# UM202.net
KiCad netlist of a schematic drawn in Altium Designer
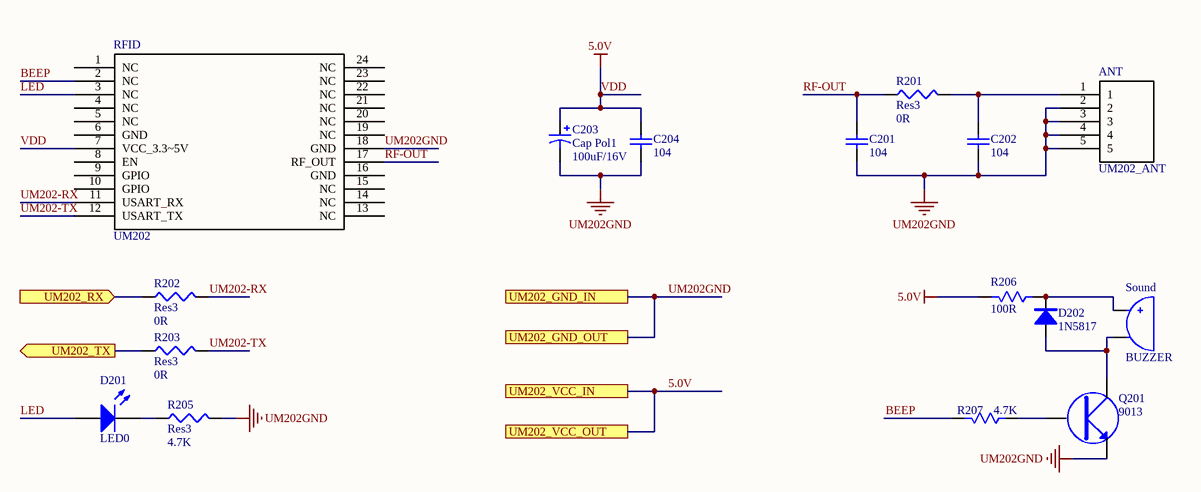
[diagram p0: UM202.SchDoc]

(export (version "E")
  (design (tool "Eeschema 10.0.6"))
  (components
    (comp (ref "ANT") (value "UM202_ANT") (libsource (lib "Schlib1") (part "UM202_ANT")))
    (comp (ref "C201")
      (value "104")
      (footprint "RAD-0.3")
      (description "Capacitor")
      (fields (field (name "PUBLISHER") "Altium Limited"))
      (libsource (lib "Miscellaneous Devices") (part "Cap"))
    )
    (comp (ref "C202")
      (value "104")
      (footprint "RAD-0.3")
      (description "Capacitor")
      (fields (field (name "PUBLISHER") "Altium Limited"))
      (libsource (lib "Miscellaneous Devices") (part "Cap"))
    )
    (comp (ref "C203")
      (value "Cap Pol1")
      (footprint "RB7.6-15")
      (description "Polarized Capacitor (Radial)")
      (fields (field (name "ALTIUM_VALUE") "100uF/16V") (field (name "PUBLISHER") "Altium Limited"))
      (libsource (lib "Miscellaneous Devices") (part "Cap Pol1"))
    )
    (comp (ref "C204")
      (value "104")
      (footprint "RAD-0.3")
      (description "Capacitor")
      (fields (field (name "PUBLISHER") "Altium Limited"))
      (libsource (lib "Miscellaneous Devices") (part "Cap"))
    )
    (comp (ref "D201")
      (value "LED0")
      (footprint "LED-0")
      (description "Typical INFRARED GaAs LED")
      (fields (field (name "PUBLISHER") "Altium Limited"))
      (libsource (lib "Miscellaneous Devices") (part "LED0"))
    )
    (comp (ref "D202")
      (value "1N5817")
      (footprint "YUWEI_LIB:SOD-323")
      (description "Diode")
      (libsource (lib "*") (part "DIODE"))
    )
    (comp (ref "Q201") (value "9013") (libsource (lib "Schlib1") (part "9013")))
    (comp (ref "R201")
      (value "Res3")
      (footprint "J1-0603")
      (description "Resistor")
      (fields (field (name "ALTIUM_VALUE") "0R") (field (name "PUBLISHER") "Altium Limited"))
      (libsource (lib "Miscellaneous Devices") (part "Res3"))
    )
    (comp (ref "R202")
      (value "Res3")
      (footprint "J1-0603")
      (description "Resistor")
      (fields (field (name "ALTIUM_VALUE") "0R") (field (name "PUBLISHER") "Altium Limited"))
      (libsource (lib "Miscellaneous Devices") (part "Res3"))
    )
    (comp (ref "R203")
      (value "Res3")
      (footprint "J1-0603")
      (description "Resistor")
      (fields (field (name "ALTIUM_VALUE") "0R") (field (name "PUBLISHER") "Altium Limited"))
      (libsource (lib "Miscellaneous Devices") (part "Res3"))
    )
    (comp (ref "R205")
      (value "Res3")
      (footprint "J1-0603")
      (description "Resistor")
      (fields (field (name "ALTIUM_VALUE") "4.7K") (field (name "PUBLISHER") "Altium Limited"))
      (libsource (lib "Miscellaneous Devices") (part "Res3"))
    )
    (comp (ref "R206") (value "100R") (footprint "YUWEI_LIB:0603R-M") (libsource (lib "*") (part "RES1")))
    (comp (ref "R207") (value "4.7K") (footprint "YUWEI_LIB:0603R-M") (libsource (lib "*") (part "RES1")))
    (comp (ref "RFID") (value "UM202") (libsource (lib "Schlib1") (part "UM202")))
    (comp (ref "Sound")
      (value "BUZZER")
      (footprint "YUWEI_LIB:BUZZER-SMD")
      (description "Buzzer")
      (libsource (lib "*") (part "BUZZER"))
    )
  )
  (nets
    (net (code "1") (name "/BEEP") (class "Default")
      (node (ref "R207") (pin "1") (pinfunction "1_1") (pintype "passive"))
      (node (ref "RFID") (pin "2") (pinfunction "NC_2") (pintype "passive"))
    )
    (net (code "2") (name "/LED") (class "Default")
      (node (ref "D201") (pin "1") (pinfunction "A_1") (pintype "passive"))
      (node (ref "RFID") (pin "3") (pinfunction "NC_3") (pintype "passive"))
    )
    (net (code "3") (name "/RF-OUT") (class "Default")
      (node (ref "C201") (pin "2") (pinfunction "2_2") (pintype "passive"))
      (node (ref "R201") (pin "1") (pinfunction "1_1") (pintype "passive"))
      (node (ref "RFID") (pin "17") (pinfunction "RF_OUT_17") (pintype "passive"))
    )
    (net (code "4") (name "/UM202-RX") (class "Default")
      (node (ref "R202") (pin "2") (pinfunction "2_2") (pintype "passive"))
      (node (ref "RFID") (pin "11") (pinfunction "USART_RX_11") (pintype "passive"))
    )
    (net (code "5") (name "/UM202-TX") (class "Default")
      (node (ref "R203") (pin "2") (pinfunction "2_2") (pintype "passive"))
      (node (ref "RFID") (pin "12") (pinfunction "USART_TX_12") (pintype "passive"))
    )
    (net (code "6") (name "/UM202_RX") (class "Default")
      (node (ref "R202") (pin "1") (pinfunction "1_1") (pintype "passive"))
    )
    (net (code "7") (name "/UM202_TX") (class "Default")
      (node (ref "R203") (pin "1") (pinfunction "1_1") (pintype "passive"))
    )
    (net (code "8") (name "5.0V") (class "Default")
      (node (ref "C203") (pin "1") (pinfunction "1_1") (pintype "passive"))
      (node (ref "C204") (pin "2") (pinfunction "2_2") (pintype "passive"))
      (node (ref "R206") (pin "1") (pinfunction "1_1") (pintype "passive"))
      (node (ref "RFID") (pin "7") (pinfunction "VCC_3.3~5V_7") (pintype "passive"))
    )
    (net (code "9") (name "Net-(ANT-Pad1)") (class "Default")
      (node (ref "ANT") (pin "1") (pinfunction "1_1") (pintype "passive"))
      (node (ref "C202") (pin "2") (pinfunction "2_2") (pintype "passive"))
      (node (ref "R201") (pin "2") (pinfunction "2_2") (pintype "passive"))
    )
    (net (code "10") (name "Net-(D201-K)") (class "Default")
      (node (ref "D201") (pin "2") (pinfunction "K_2") (pintype "passive"))
      (node (ref "R205") (pin "1") (pinfunction "1_1") (pintype "passive"))
    )
    (net (code "11") (name "Net-(Q201-Pad1)") (class "Default")
      (node (ref "Q201") (pin "1") (pinfunction "1_1") (pintype "passive"))
      (node (ref "R207") (pin "2") (pinfunction "2_2") (pintype "passive"))
    )
    (net (code "12") (name "Net-(Sound-A)") (class "Default")
      (node (ref "D202") (pin "C") (pinfunction "C_C") (pintype "passive"))
      (node (ref "R206") (pin "2") (pinfunction "2_2") (pintype "passive"))
      (node (ref "Sound") (pin "1") (pinfunction "A_1") (pintype "passive"))
    )
    (net (code "13") (name "Net-(Sound-B)") (class "Default")
      (node (ref "D202") (pin "A") (pinfunction "A_A") (pintype "passive"))
      (node (ref "Q201") (pin "3") (pinfunction "3_3") (pintype "passive"))
      (node (ref "Sound") (pin "2") (pinfunction "B_2") (pintype "passive"))
    )
    (net (code "14") (name "UM202GND") (class "Default")
      (node (ref "ANT") (pin "2") (pinfunction "2_2") (pintype "passive"))
      (node (ref "ANT") (pin "3") (pinfunction "3_3") (pintype "passive"))
      (node (ref "ANT") (pin "4") (pinfunction "4_4") (pintype "passive"))
      (node (ref "ANT") (pin "5") (pinfunction "5_5") (pintype "passive"))
      (node (ref "C201") (pin "1") (pinfunction "1_1") (pintype "passive"))
      (node (ref "C202") (pin "1") (pinfunction "1_1") (pintype "passive"))
      (node (ref "C203") (pin "2") (pinfunction "2_2") (pintype "passive"))
      (node (ref "C204") (pin "1") (pinfunction "1_1") (pintype "passive"))
      (node (ref "Q201") (pin "2") (pinfunction "2_2") (pintype "passive"))
      (node (ref "R205") (pin "2") (pinfunction "2_2") (pintype "passive"))
      (node (ref "RFID") (pin "18") (pinfunction "GND_18") (pintype "passive"))
    )
    (net (code "15") (name "unconnected-(RFID-EN-Pad8)") (class "Default")
      (node (ref "RFID") (pin "8") (pinfunction "EN_8") (pintype "passive"))
    )
    (net (code "16") (name "unconnected-(RFID-GND-Pad6)") (class "Default")
      (node (ref "RFID") (pin "6") (pinfunction "GND_6") (pintype "passive"))
    )
    (net (code "17") (name "unconnected-(RFID-GND-Pad16)") (class "Default")
      (node (ref "RFID") (pin "16") (pinfunction "GND_16") (pintype "passive"))
    )
    (net (code "18") (name "unconnected-(RFID-GPIO-Pad9)") (class "Default")
      (node (ref "RFID") (pin "9") (pinfunction "GPIO_9") (pintype "passive"))
    )
    (net (code "19") (name "unconnected-(RFID-GPIO-Pad10)") (class "Default")
      (node (ref "RFID") (pin "10") (pinfunction "GPIO_10") (pintype "passive"))
    )
    (net (code "20") (name "unconnected-(RFID-NC-Pad1)") (class "Default")
      (node (ref "RFID") (pin "1") (pinfunction "NC_1") (pintype "passive"))
    )
    (net (code "21") (name "unconnected-(RFID-NC-Pad4)") (class "Default")
      (node (ref "RFID") (pin "4") (pinfunction "NC_4") (pintype "passive"))
    )
    (net (code "22") (name "unconnected-(RFID-NC-Pad5)") (class "Default")
      (node (ref "RFID") (pin "5") (pinfunction "NC_5") (pintype "passive"))
    )
    (net (code "23") (name "unconnected-(RFID-NC-Pad13)") (class "Default")
      (node (ref "RFID") (pin "13") (pinfunction "NC_13") (pintype "passive"))
    )
    (net (code "24") (name "unconnected-(RFID-NC-Pad14)") (class "Default")
      (node (ref "RFID") (pin "14") (pinfunction "NC_14") (pintype "passive"))
    )
    (net (code "25") (name "unconnected-(RFID-NC-Pad15)") (class "Default")
      (node (ref "RFID") (pin "15") (pinfunction "NC_15") (pintype "passive"))
    )
    (net (code "26") (name "unconnected-(RFID-NC-Pad19)") (class "Default")
      (node (ref "RFID") (pin "19") (pinfunction "NC_19") (pintype "passive"))
    )
    (net (code "27") (name "unconnected-(RFID-NC-Pad20)") (class "Default")
      (node (ref "RFID") (pin "20") (pinfunction "NC_20") (pintype "passive"))
    )
    (net (code "28") (name "unconnected-(RFID-NC-Pad21)") (class "Default")
      (node (ref "RFID") (pin "21") (pinfunction "NC_21") (pintype "passive"))
    )
    (net (code "29") (name "unconnected-(RFID-NC-Pad22)") (class "Default")
      (node (ref "RFID") (pin "22") (pinfunction "NC_22") (pintype "passive"))
    )
    (net (code "30") (name "unconnected-(RFID-NC-Pad23)") (class "Default")
      (node (ref "RFID") (pin "23") (pinfunction "NC_23") (pintype "passive"))
    )
    (net (code "31") (name "unconnected-(RFID-NC-Pad24)") (class "Default")
      (node (ref "RFID") (pin "24") (pinfunction "NC_24") (pintype "passive"))
    )
  )
)
